# SOS-v2.net
KiCad netlist of a schematic drawn in EAGLE
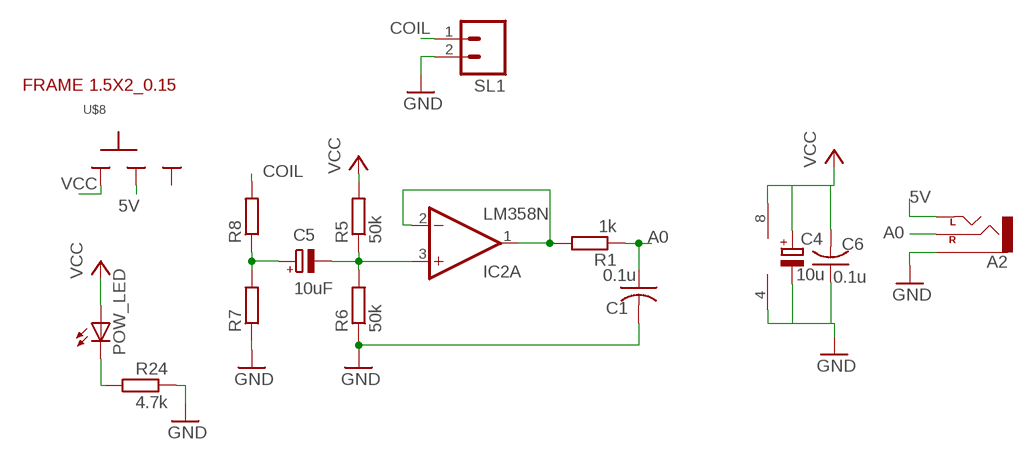
[diagram p0: schematic, sheet 1]

(export (version "E")
  (design (tool "Eeschema 10.0.6"))
  (components
    (comp (ref "A2")
      (value "AUX-CONNECTOR_CEDT_JANUARY_2015_V5_AUDIO-JACKPTH")
      (footprint "eagle-import:AUX-CONNECTOR_CEDT_JANUARY_2015_V5_AUDIO-JACK")
      (libsource (lib "eagle-import") (part "AUX-CONNECTOR_CEDT_JANUARY_2015_V5_AUDIO-JACKPTH"))
    )
    (comp (ref "C1")
      (value "0.1u")
      (footprint "eagle-import:C025-024X044")
      (libsource (lib "eagle-import") (part "C-US025-024X044"))
    )
    (comp (ref "C4")
      (value "10u")
      (footprint "eagle-import:E2,5-5")
      (libsource (lib "eagle-import") (part "CPOL-EUE2.5-5"))
    )
    (comp (ref "C5")
      (value "10uF")
      (footprint "eagle-import:E2,5-6")
      (libsource (lib "eagle-import") (part "CPOL-EUE2.5-6"))
    )
    (comp (ref "C6")
      (value "0.1u")
      (footprint "eagle-import:C025-024X044")
      (libsource (lib "eagle-import") (part "C-US025-024X044"))
    )
    (comp (ref "IC2")
      (value "LM358N")
      (footprint "eagle-import:DIL08")
      (libsource (lib "eagle-import") (part "LM358N"))
    )
    (comp (ref "POW_LED")
      (value "LED3MM")
      (footprint "eagle-import:LED3MM")
      (libsource (lib "eagle-import") (part "LED3MM"))
    )
    (comp (ref "R1")
      (value "1k")
      (footprint "eagle-import:0204_7")
      (libsource (lib "eagle-import") (part "R-EU_0204/7"))
    )
    (comp (ref "R5")
      (value "50k")
      (footprint "eagle-import:0204_7")
      (libsource (lib "eagle-import") (part "R-EU_0204/7"))
    )
    (comp (ref "R6")
      (value "50k")
      (footprint "eagle-import:0204_7")
      (libsource (lib "eagle-import") (part "R-EU_0204/7"))
    )
    (comp (ref "R7")
      (value "R-EU_0204/7")
      (footprint "eagle-import:0204_7")
      (libsource (lib "eagle-import") (part "R-EU_0204/7"))
    )
    (comp (ref "R8")
      (value "R-EU_0204/7")
      (footprint "eagle-import:0204_7")
      (libsource (lib "eagle-import") (part "R-EU_0204/7"))
    )
    (comp (ref "R24")
      (value "4.7k")
      (footprint "eagle-import:0204_7")
      (libsource (lib "eagle-import") (part "R-EU_0204/7"))
    )
    (comp (ref "SL1")
      (value "M02")
      (footprint "eagle-import:02P")
      (libsource (lib "eagle-import") (part "M02"))
    )
    (comp (ref "U$1")
      (value "FRAME_1.5X2_RAD_0.15")
      (footprint "eagle-import:FRAME_1.5X2_RAD_0.15")
      (libsource (lib "eagle-import") (part "FRAME_1.5X2_RAD_0.15"))
    )
    (comp (ref "U$8")
      (value "SLIDESWITCH-BIG")
      (footprint "eagle-import:BIGSWITCH")
      (libsource (lib "eagle-import") (part "SLIDESWITCH-BIG"))
    )
  )
  (nets
    (net (code "1") (name "/5V") (class "Default")
      (node (ref "A2") (pin "TIP") (pinfunction "LEFT_TIP") (pintype "bidirectional"))
      (node (ref "U$8") (pin "2") (pinfunction "2_2") (pintype "bidirectional"))
    )
    (net (code "2") (name "/A0") (class "Default")
      (node (ref "A2") (pin "RING") (pinfunction "RIGHT_RING") (pintype "bidirectional"))
      (node (ref "C1") (pin "1") (pinfunction "1_1") (pintype "passive"))
      (node (ref "R1") (pin "1") (pinfunction "1_1") (pintype "passive"))
    )
    (net (code "3") (name "/COIL") (class "Default")
      (node (ref "R8") (pin "2") (pinfunction "2_2") (pintype "passive"))
      (node (ref "SL1") (pin "1") (pinfunction "1_1") (pintype "passive"))
    )
    (net (code "4") (name "GND") (class "Default")
      (node (ref "A2") (pin "SLEEVE") (pinfunction "SLEEVE_SLEEVE") (pintype "bidirectional"))
      (node (ref "C1") (pin "2") (pinfunction "2_2") (pintype "passive"))
      (node (ref "C4") (pin "-") (pinfunction "-_-") (pintype "passive"))
      (node (ref "C6") (pin "1") (pinfunction "1_1") (pintype "passive"))
      (node (ref "IC2") (pin "4") (pinfunction "V-_4") (pintype "power_in"))
      (node (ref "R24") (pin "1") (pinfunction "1_1") (pintype "passive"))
      (node (ref "R6") (pin "1") (pinfunction "1_1") (pintype "passive"))
      (node (ref "R7") (pin "1") (pinfunction "1_1") (pintype "passive"))
      (node (ref "SL1") (pin "2") (pinfunction "2_2") (pintype "passive"))
    )
    (net (code "5") (name "Net-(C5-Pad+)") (class "Default")
      (node (ref "C5") (pin "+") (pinfunction "+_+") (pintype "passive"))
      (node (ref "R7") (pin "2") (pinfunction "2_2") (pintype "passive"))
      (node (ref "R8") (pin "1") (pinfunction "1_1") (pintype "passive"))
    )
    (net (code "6") (name "Net-(IC2A-+IN)") (class "Default")
      (node (ref "C5") (pin "-") (pinfunction "-_-") (pintype "passive"))
      (node (ref "IC2") (pin "3") (pinfunction "+IN_3") (pintype "input"))
      (node (ref "R5") (pin "1") (pinfunction "1_1") (pintype "passive"))
      (node (ref "R6") (pin "2") (pinfunction "2_2") (pintype "passive"))
    )
    (net (code "7") (name "Net-(IC2A--IN)") (class "Default")
      (node (ref "IC2") (pin "1") (pinfunction "OUT_1") (pintype "output"))
      (node (ref "IC2") (pin "2") (pinfunction "-IN_2") (pintype "input"))
      (node (ref "R1") (pin "2") (pinfunction "2_2") (pintype "passive"))
    )
    (net (code "8") (name "Net-(POW_LED-C)") (class "Default")
      (node (ref "POW_LED") (pin "K") (pinfunction "C_K") (pintype "passive"))
      (node (ref "R24") (pin "2") (pinfunction "2_2") (pintype "passive"))
    )
    (net (code "9") (name "VCC") (class "Default")
      (node (ref "C4") (pin "+") (pinfunction "+_+") (pintype "passive"))
      (node (ref "C6") (pin "2") (pinfunction "2_2") (pintype "passive"))
      (node (ref "IC2") (pin "8") (pinfunction "V+_8") (pintype "power_in"))
      (node (ref "POW_LED") (pin "A") (pinfunction "A_A") (pintype "passive"))
      (node (ref "R5") (pin "2") (pinfunction "2_2") (pintype "passive"))
      (node (ref "U$8") (pin "1") (pinfunction "1_1") (pintype "bidirectional"))
    )
    (net (code "10") (name "unconnected-(U$8-Pad3)") (class "Default")
      (node (ref "U$8") (pin "3") (pinfunction "3_3") (pintype "bidirectional"))
    )
  )
)
